# Macropad.net
KiCad netlist of a schematic drawn in EAGLE
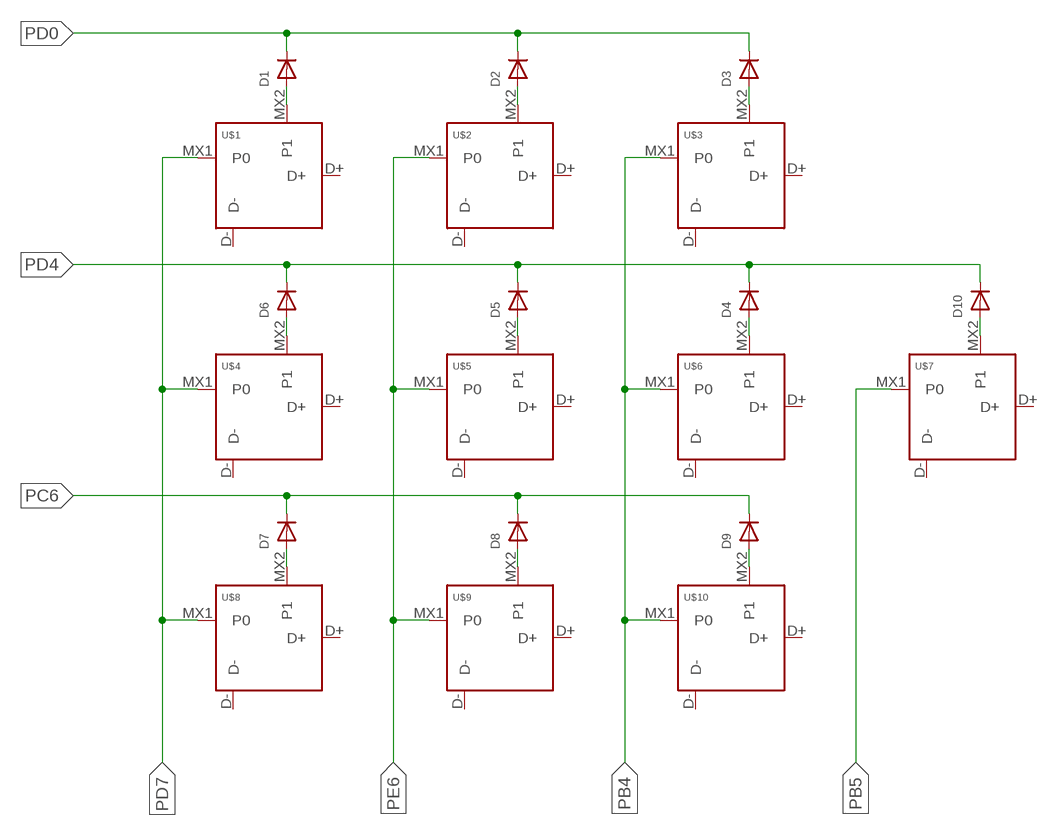
[diagram p0: schematic, sheet 1]

(export (version "E")
  (design (tool "Eeschema 10.0.6"))
  (components
    (comp (ref "D1")
      (value "DIODEDO-1N4148")
      (footprint "eagle-import:DO-1N4148")
      (libsource (lib "eagle-import") (part "DIODEDO-1N4148"))
    )
    (comp (ref "D2")
      (value "DIODEDO-1N4148")
      (footprint "eagle-import:DO-1N4148")
      (libsource (lib "eagle-import") (part "DIODEDO-1N4148"))
    )
    (comp (ref "D3")
      (value "DIODEDO-1N4148")
      (footprint "eagle-import:DO-1N4148")
      (libsource (lib "eagle-import") (part "DIODEDO-1N4148"))
    )
    (comp (ref "D4")
      (value "DIODEDO-1N4148")
      (footprint "eagle-import:DO-1N4148")
      (libsource (lib "eagle-import") (part "DIODEDO-1N4148"))
    )
    (comp (ref "D5")
      (value "DIODEDO-1N4148")
      (footprint "eagle-import:DO-1N4148")
      (libsource (lib "eagle-import") (part "DIODEDO-1N4148"))
    )
    (comp (ref "D6")
      (value "DIODEDO-1N4148")
      (footprint "eagle-import:DO-1N4148")
      (libsource (lib "eagle-import") (part "DIODEDO-1N4148"))
    )
    (comp (ref "D7")
      (value "DIODEDO-1N4148")
      (footprint "eagle-import:DO-1N4148")
      (libsource (lib "eagle-import") (part "DIODEDO-1N4148"))
    )
    (comp (ref "D8")
      (value "DIODEDO-1N4148")
      (footprint "eagle-import:DO-1N4148")
      (libsource (lib "eagle-import") (part "DIODEDO-1N4148"))
    )
    (comp (ref "D9")
      (value "DIODEDO-1N4148")
      (footprint "eagle-import:DO-1N4148")
      (libsource (lib "eagle-import") (part "DIODEDO-1N4148"))
    )
    (comp (ref "D10")
      (value "DIODEDO-1N4148")
      (footprint "eagle-import:DO-1N4148")
      (libsource (lib "eagle-import") (part "DIODEDO-1N4148"))
    )
    (comp (ref "U$1")
      (value "KEYSWITCH-DIODE-MX-1U-DIODE")
      (footprint "eagle-import:MX-1U-DIODE")
      (libsource (lib "eagle-import") (part "KEYSWITCH-DIODE-MX-1U-DIODE"))
    )
    (comp (ref "U$2")
      (value "KEYSWITCH-DIODE-MX-1U-DIODE")
      (footprint "eagle-import:MX-1U-DIODE")
      (libsource (lib "eagle-import") (part "KEYSWITCH-DIODE-MX-1U-DIODE"))
    )
    (comp (ref "U$3")
      (value "KEYSWITCH-DIODE-MX-1U-DIODE")
      (footprint "eagle-import:MX-1U-DIODE")
      (libsource (lib "eagle-import") (part "KEYSWITCH-DIODE-MX-1U-DIODE"))
    )
    (comp (ref "U$4")
      (value "KEYSWITCH-DIODE-MX-1U-DIODE")
      (footprint "eagle-import:MX-1U-DIODE")
      (libsource (lib "eagle-import") (part "KEYSWITCH-DIODE-MX-1U-DIODE"))
    )
    (comp (ref "U$5")
      (value "KEYSWITCH-DIODE-MX-1U-DIODE")
      (footprint "eagle-import:MX-1U-DIODE")
      (libsource (lib "eagle-import") (part "KEYSWITCH-DIODE-MX-1U-DIODE"))
    )
    (comp (ref "U$6")
      (value "KEYSWITCH-DIODE-MX-1U-DIODE")
      (footprint "eagle-import:MX-1U-DIODE")
      (libsource (lib "eagle-import") (part "KEYSWITCH-DIODE-MX-1U-DIODE"))
    )
    (comp (ref "U$7")
      (value "KEYSWITCH-DIODE-MX-1U-DIODE")
      (footprint "eagle-import:MX-1U-DIODE")
      (libsource (lib "eagle-import") (part "KEYSWITCH-DIODE-MX-1U-DIODE"))
    )
    (comp (ref "U$8")
      (value "KEYSWITCH-DIODE-MX-1U-DIODE")
      (footprint "eagle-import:MX-1U-DIODE")
      (libsource (lib "eagle-import") (part "KEYSWITCH-DIODE-MX-1U-DIODE"))
    )
    (comp (ref "U$9")
      (value "KEYSWITCH-DIODE-MX-1U-DIODE")
      (footprint "eagle-import:MX-1U-DIODE")
      (libsource (lib "eagle-import") (part "KEYSWITCH-DIODE-MX-1U-DIODE"))
    )
    (comp (ref "U$10")
      (value "KEYSWITCH-DIODE-MX-1U-DIODE")
      (footprint "eagle-import:MX-1U-DIODE")
      (libsource (lib "eagle-import") (part "KEYSWITCH-DIODE-MX-1U-DIODE"))
    )
  )
  (nets
    (net (code "1") (name "Net-(U$1-P1)") (class "Default")
      (node (ref "D1") (pin "A") (pinfunction "A_A") (pintype "passive"))
      (node (ref "U$1") (pin "MX2") (pinfunction "P1_MX2") (pintype "bidirectional"))
    )
    (net (code "2") (name "Net-(U$2-P1)") (class "Default")
      (node (ref "D2") (pin "A") (pinfunction "A_A") (pintype "passive"))
      (node (ref "U$2") (pin "MX2") (pinfunction "P1_MX2") (pintype "bidirectional"))
    )
    (net (code "3") (name "Net-(U$3-P1)") (class "Default")
      (node (ref "D3") (pin "A") (pinfunction "A_A") (pintype "passive"))
      (node (ref "U$3") (pin "MX2") (pinfunction "P1_MX2") (pintype "bidirectional"))
    )
    (net (code "4") (name "Net-(U$4-P1)") (class "Default")
      (node (ref "D6") (pin "A") (pinfunction "A_A") (pintype "passive"))
      (node (ref "U$4") (pin "MX2") (pinfunction "P1_MX2") (pintype "bidirectional"))
    )
    (net (code "5") (name "Net-(U$5-P1)") (class "Default")
      (node (ref "D5") (pin "A") (pinfunction "A_A") (pintype "passive"))
      (node (ref "U$5") (pin "MX2") (pinfunction "P1_MX2") (pintype "bidirectional"))
    )
    (net (code "6") (name "Net-(U$6-P1)") (class "Default")
      (node (ref "D4") (pin "A") (pinfunction "A_A") (pintype "passive"))
      (node (ref "U$6") (pin "MX2") (pinfunction "P1_MX2") (pintype "bidirectional"))
    )
    (net (code "7") (name "Net-(U$7-P1)") (class "Default")
      (node (ref "D10") (pin "A") (pinfunction "A_A") (pintype "passive"))
      (node (ref "U$7") (pin "MX2") (pinfunction "P1_MX2") (pintype "bidirectional"))
    )
    (net (code "8") (name "Net-(U$8-P1)") (class "Default")
      (node (ref "D7") (pin "A") (pinfunction "A_A") (pintype "passive"))
      (node (ref "U$8") (pin "MX2") (pinfunction "P1_MX2") (pintype "bidirectional"))
    )
    (net (code "9") (name "Net-(U$9-P1)") (class "Default")
      (node (ref "D8") (pin "A") (pinfunction "A_A") (pintype "passive"))
      (node (ref "U$9") (pin "MX2") (pinfunction "P1_MX2") (pintype "bidirectional"))
    )
    (net (code "10") (name "Net-(U$10-P1)") (class "Default")
      (node (ref "D9") (pin "A") (pinfunction "A_A") (pintype "passive"))
      (node (ref "U$10") (pin "MX2") (pinfunction "P1_MX2") (pintype "bidirectional"))
    )
    (net (code "11") (name "PB4") (class "Default")
      (node (ref "U$10") (pin "MX1") (pinfunction "P0_MX1") (pintype "bidirectional"))
      (node (ref "U$3") (pin "MX1") (pinfunction "P0_MX1") (pintype "bidirectional"))
      (node (ref "U$6") (pin "MX1") (pinfunction "P0_MX1") (pintype "bidirectional"))
    )
    (net (code "12") (name "PB5") (class "Default")
      (node (ref "U$7") (pin "MX1") (pinfunction "P0_MX1") (pintype "bidirectional"))
    )
    (net (code "13") (name "PC6") (class "Default")
      (node (ref "D7") (pin "C") (pinfunction "C_C") (pintype "passive"))
      (node (ref "D8") (pin "C") (pinfunction "C_C") (pintype "passive"))
      (node (ref "D9") (pin "C") (pinfunction "C_C") (pintype "passive"))
    )
    (net (code "14") (name "PD0") (class "Default")
      (node (ref "D1") (pin "C") (pinfunction "C_C") (pintype "passive"))
      (node (ref "D2") (pin "C") (pinfunction "C_C") (pintype "passive"))
      (node (ref "D3") (pin "C") (pinfunction "C_C") (pintype "passive"))
    )
    (net (code "15") (name "PD4") (class "Default")
      (node (ref "D10") (pin "C") (pinfunction "C_C") (pintype "passive"))
      (node (ref "D4") (pin "C") (pinfunction "C_C") (pintype "passive"))
      (node (ref "D5") (pin "C") (pinfunction "C_C") (pintype "passive"))
      (node (ref "D6") (pin "C") (pinfunction "C_C") (pintype "passive"))
    )
    (net (code "16") (name "PD7") (class "Default")
      (node (ref "U$1") (pin "MX1") (pinfunction "P0_MX1") (pintype "bidirectional"))
      (node (ref "U$4") (pin "MX1") (pinfunction "P0_MX1") (pintype "bidirectional"))
      (node (ref "U$8") (pin "MX1") (pinfunction "P0_MX1") (pintype "bidirectional"))
    )
    (net (code "17") (name "PE6") (class "Default")
      (node (ref "U$2") (pin "MX1") (pinfunction "P0_MX1") (pintype "bidirectional"))
      (node (ref "U$5") (pin "MX1") (pinfunction "P0_MX1") (pintype "bidirectional"))
      (node (ref "U$9") (pin "MX1") (pinfunction "P0_MX1") (pintype "bidirectional"))
    )
    (net (code "18") (name "unconnected-(U$1-PadD+)") (class "Default")
      (node (ref "U$1") (pin "D+") (pinfunction "D+_D+") (pintype "bidirectional"))
    )
    (net (code "19") (name "unconnected-(U$1-PadD-)") (class "Default")
      (node (ref "U$1") (pin "D-") (pinfunction "D-_D-") (pintype "bidirectional"))
    )
    (net (code "20") (name "unconnected-(U$2-PadD+)") (class "Default")
      (node (ref "U$2") (pin "D+") (pinfunction "D+_D+") (pintype "bidirectional"))
    )
    (net (code "21") (name "unconnected-(U$2-PadD-)") (class "Default")
      (node (ref "U$2") (pin "D-") (pinfunction "D-_D-") (pintype "bidirectional"))
    )
    (net (code "22") (name "unconnected-(U$3-PadD+)") (class "Default")
      (node (ref "U$3") (pin "D+") (pinfunction "D+_D+") (pintype "bidirectional"))
    )
    (net (code "23") (name "unconnected-(U$3-PadD-)") (class "Default")
      (node (ref "U$3") (pin "D-") (pinfunction "D-_D-") (pintype "bidirectional"))
    )
    (net (code "24") (name "unconnected-(U$4-PadD+)") (class "Default")
      (node (ref "U$4") (pin "D+") (pinfunction "D+_D+") (pintype "bidirectional"))
    )
    (net (code "25") (name "unconnected-(U$4-PadD-)") (class "Default")
      (node (ref "U$4") (pin "D-") (pinfunction "D-_D-") (pintype "bidirectional"))
    )
    (net (code "26") (name "unconnected-(U$5-PadD+)") (class "Default")
      (node (ref "U$5") (pin "D+") (pinfunction "D+_D+") (pintype "bidirectional"))
    )
    (net (code "27") (name "unconnected-(U$5-PadD-)") (class "Default")
      (node (ref "U$5") (pin "D-") (pinfunction "D-_D-") (pintype "bidirectional"))
    )
    (net (code "28") (name "unconnected-(U$6-PadD+)") (class "Default")
      (node (ref "U$6") (pin "D+") (pinfunction "D+_D+") (pintype "bidirectional"))
    )
    (net (code "29") (name "unconnected-(U$6-PadD-)") (class "Default")
      (node (ref "U$6") (pin "D-") (pinfunction "D-_D-") (pintype "bidirectional"))
    )
    (net (code "30") (name "unconnected-(U$7-PadD+)") (class "Default")
      (node (ref "U$7") (pin "D+") (pinfunction "D+_D+") (pintype "bidirectional"))
    )
    (net (code "31") (name "unconnected-(U$7-PadD-)") (class "Default")
      (node (ref "U$7") (pin "D-") (pinfunction "D-_D-") (pintype "bidirectional"))
    )
    (net (code "32") (name "unconnected-(U$8-PadD+)") (class "Default")
      (node (ref "U$8") (pin "D+") (pinfunction "D+_D+") (pintype "bidirectional"))
    )
    (net (code "33") (name "unconnected-(U$8-PadD-)") (class "Default")
      (node (ref "U$8") (pin "D-") (pinfunction "D-_D-") (pintype "bidirectional"))
    )
    (net (code "34") (name "unconnected-(U$9-PadD+)") (class "Default")
      (node (ref "U$9") (pin "D+") (pinfunction "D+_D+") (pintype "bidirectional"))
    )
    (net (code "35") (name "unconnected-(U$9-PadD-)") (class "Default")
      (node (ref "U$9") (pin "D-") (pinfunction "D-_D-") (pintype "bidirectional"))
    )
    (net (code "36") (name "unconnected-(U$10-PadD+)") (class "Default")
      (node (ref "U$10") (pin "D+") (pinfunction "D+_D+") (pintype "bidirectional"))
    )
    (net (code "37") (name "unconnected-(U$10-PadD-)") (class "Default")
      (node (ref "U$10") (pin "D-") (pinfunction "D-_D-") (pintype "bidirectional"))
    )
  )
)
